# current_limiter.net
KiCad netlist of a schematic drawn in EAGLE
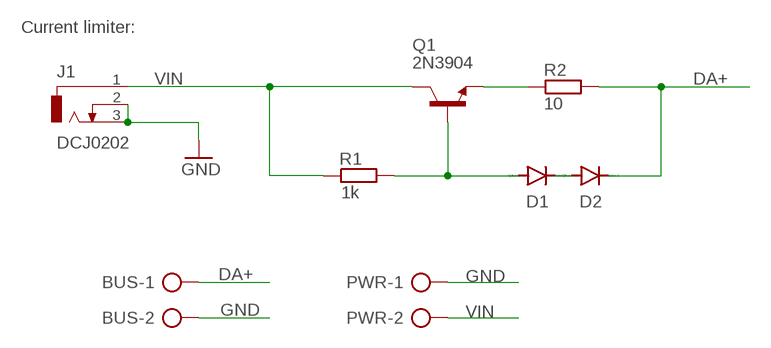
[diagram p0: schematic, sheet 1]

(export (version "E")
  (design (tool "Eeschema 10.0.6"))
  (components
    (comp (ref "BUS")
      (value "AK500/2")
      (footprint "eagle-import:AK500_2")
      (libsource (lib "eagle-import") (part "AK500/2"))
    )
    (comp (ref "D1")
      (value "1N4004")
      (footprint "eagle-import:DO41-10")
      (libsource (lib "eagle-import") (part "1N4004"))
    )
    (comp (ref "D2")
      (value "1N4004")
      (footprint "eagle-import:DO41-10")
      (libsource (lib "eagle-import") (part "1N4004"))
    )
    (comp (ref "J1")
      (value "DCJ0202")
      (footprint "eagle-import:DCJ0202")
      (libsource (lib "eagle-import") (part "DCJ0202"))
    )
    (comp (ref "PWR")
      (value "AK500/2")
      (footprint "eagle-import:AK500_2")
      (libsource (lib "eagle-import") (part "AK500/2"))
    )
    (comp (ref "Q1")
      (value "2N3904")
      (footprint "eagle-import:TO92-EBC")
      (libsource (lib "eagle-import") (part "BC449"))
    )
    (comp (ref "R1")
      (value "1k")
      (footprint "eagle-import:0207_10")
      (libsource (lib "eagle-import") (part "R-EU_0207/10"))
    )
    (comp (ref "R2")
      (value "10")
      (footprint "eagle-import:0207_10")
      (libsource (lib "eagle-import") (part "R-EU_0207/10"))
    )
  )
  (nets
    (net (code "1") (name "/DA+") (class "Default")
      (node (ref "BUS") (pin "1") (pinfunction "KL_1") (pintype "passive"))
      (node (ref "D2") (pin "C") (pinfunction "C_C") (pintype "passive"))
      (node (ref "R2") (pin "2") (pinfunction "2_2") (pintype "passive"))
    )
    (net (code "2") (name "/VIN") (class "Default")
      (node (ref "J1") (pin "1") (pinfunction "1_1") (pintype "passive"))
      (node (ref "PWR") (pin "2") (pinfunction "KL_2") (pintype "passive"))
      (node (ref "Q1") (pin "C") (pinfunction "C_C") (pintype "passive"))
      (node (ref "R1") (pin "1") (pinfunction "1_1") (pintype "passive"))
    )
    (net (code "3") (name "GND") (class "Default")
      (node (ref "BUS") (pin "2") (pinfunction "KL_2") (pintype "passive"))
      (node (ref "J1") (pin "2") (pinfunction "2_2") (pintype "passive"))
      (node (ref "J1") (pin "3") (pinfunction "3_3") (pintype "passive"))
      (node (ref "PWR") (pin "1") (pinfunction "KL_1") (pintype "passive"))
    )
    (net (code "4") (name "Net-(D1-PadA)") (class "Default")
      (node (ref "D1") (pin "A") (pinfunction "A_A") (pintype "passive"))
      (node (ref "Q1") (pin "B") (pinfunction "B_B") (pintype "passive"))
      (node (ref "R1") (pin "2") (pinfunction "2_2") (pintype "passive"))
    )
    (net (code "5") (name "Net-(D1-PadC)") (class "Default")
      (node (ref "D1") (pin "C") (pinfunction "C_C") (pintype "passive"))
      (node (ref "D2") (pin "A") (pinfunction "A_A") (pintype "passive"))
    )
    (net (code "6") (name "Net-(Q1-PadE)") (class "Default")
      (node (ref "Q1") (pin "E") (pinfunction "E_E") (pintype "passive"))
      (node (ref "R2") (pin "1") (pinfunction "1_1") (pintype "passive"))
    )
  )
)
